# AD5330_Breakout.net
KiCad netlist of a schematic drawn in EAGLE
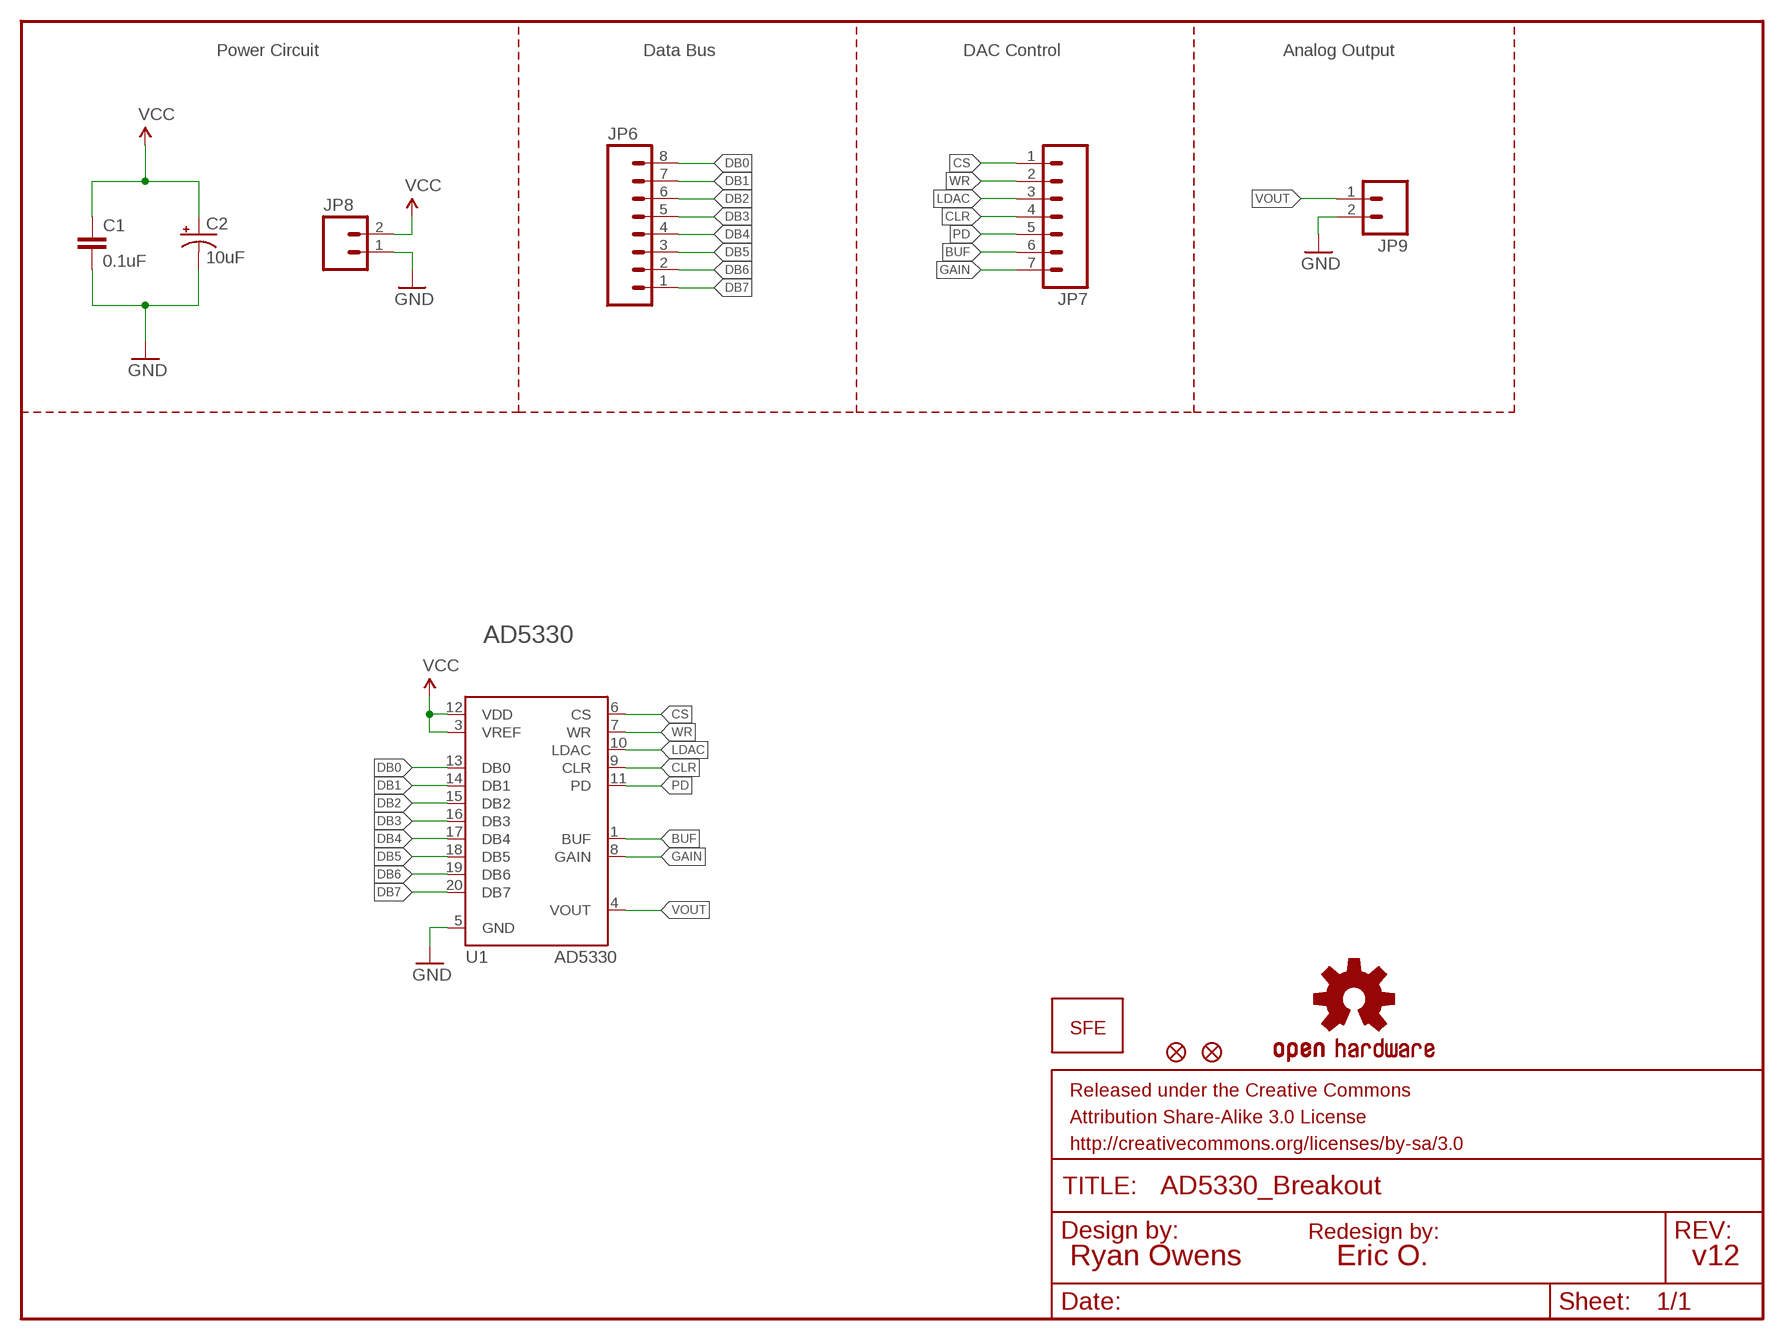
[diagram p0: schematic, sheet 1]

(export (version "E")
  (design (tool "Eeschema 10.0.6"))
  (components
    (comp (ref "C1")
      (value "0.1uF")
      (footprint "eagle-import:0603-CAP")
      (libsource (lib "eagle-import") (part "0.1UF-25V(+80/-20%)(0603)"))
    )
    (comp (ref "C2")
      (value "10uF")
      (footprint "eagle-import:EIA3216")
      (libsource (lib "eagle-import") (part "10UF-16V-10%(TANT)"))
    )
    (comp (ref "FRAME1")
      (value "FRAME-LETTER")
      (footprint "eagle-import:CREATIVE_COMMONS")
      (libsource (lib "eagle-import") (part "FRAME-LETTER"))
    )
    (comp (ref "JP1")
      (value "LOGO-SFENEW")
      (footprint "eagle-import:SFE-NEW-WEBLOGO")
      (libsource (lib "eagle-import") (part "LOGO-SFENEW"))
    )
    (comp (ref "JP2")
      (value "FIDUCIAL1X2")
      (footprint "eagle-import:FIDUCIAL-1X2")
      (libsource (lib "eagle-import") (part "FIDUCIAL1X2"))
    )
    (comp (ref "JP3")
      (value "FIDUCIAL1X2")
      (footprint "eagle-import:FIDUCIAL-1X2")
      (libsource (lib "eagle-import") (part "FIDUCIAL1X2"))
    )
    (comp (ref "JP6")
      (value "M08")
      (footprint "eagle-import:1X08")
      (libsource (lib "eagle-import") (part "M08"))
    )
    (comp (ref "JP7")
      (value "M07")
      (footprint "eagle-import:1X07")
      (libsource (lib "eagle-import") (part "M07"))
    )
    (comp (ref "JP8")
      (value "M02PTH")
      (footprint "eagle-import:1X02")
      (libsource (lib "eagle-import") (part "M02PTH"))
    )
    (comp (ref "JP9")
      (value "M02PTH")
      (footprint "eagle-import:1X02")
      (libsource (lib "eagle-import") (part "M02PTH"))
    )
    (comp (ref "LOGO1")
      (value "OSHW-LOGOS")
      (footprint "eagle-import:OSHW-LOGO-S")
      (libsource (lib "eagle-import") (part "OSHW-LOGOS"))
    )
    (comp (ref "U1")
      (value "AD5330")
      (footprint "eagle-import:TSSOP20")
      (libsource (lib "eagle-import") (part "AD5330"))
    )
  )
  (nets
    (net (code "1") (name "BUF") (class "Default")
      (node (ref "JP7") (pin "6") (pinfunction "6_6") (pintype "passive"))
      (node (ref "U1") (pin "1") (pinfunction "BUF_1") (pintype "bidirectional"))
    )
    (net (code "2") (name "CLR") (class "Default")
      (node (ref "JP7") (pin "4") (pinfunction "4_4") (pintype "passive"))
      (node (ref "U1") (pin "9") (pinfunction "CLR_9") (pintype "bidirectional"))
    )
    (net (code "3") (name "CS") (class "Default")
      (node (ref "JP7") (pin "1") (pinfunction "1_1") (pintype "passive"))
      (node (ref "U1") (pin "6") (pinfunction "CS_6") (pintype "bidirectional"))
    )
    (net (code "4") (name "DB0") (class "Default")
      (node (ref "JP6") (pin "8") (pinfunction "8_8") (pintype "passive"))
      (node (ref "U1") (pin "13") (pinfunction "DB0_13") (pintype "bidirectional"))
    )
    (net (code "5") (name "DB1") (class "Default")
      (node (ref "JP6") (pin "7") (pinfunction "7_7") (pintype "passive"))
      (node (ref "U1") (pin "14") (pinfunction "DB1_14") (pintype "bidirectional"))
    )
    (net (code "6") (name "DB2") (class "Default")
      (node (ref "JP6") (pin "6") (pinfunction "6_6") (pintype "passive"))
      (node (ref "U1") (pin "15") (pinfunction "DB2_15") (pintype "bidirectional"))
    )
    (net (code "7") (name "DB3") (class "Default")
      (node (ref "JP6") (pin "5") (pinfunction "5_5") (pintype "passive"))
      (node (ref "U1") (pin "16") (pinfunction "DB3_16") (pintype "bidirectional"))
    )
    (net (code "8") (name "DB4") (class "Default")
      (node (ref "JP6") (pin "4") (pinfunction "4_4") (pintype "passive"))
      (node (ref "U1") (pin "17") (pinfunction "DB4_17") (pintype "bidirectional"))
    )
    (net (code "9") (name "DB5") (class "Default")
      (node (ref "JP6") (pin "3") (pinfunction "3_3") (pintype "passive"))
      (node (ref "U1") (pin "18") (pinfunction "DB5_18") (pintype "bidirectional"))
    )
    (net (code "10") (name "DB6") (class "Default")
      (node (ref "JP6") (pin "2") (pinfunction "2_2") (pintype "passive"))
      (node (ref "U1") (pin "19") (pinfunction "DB6_19") (pintype "bidirectional"))
    )
    (net (code "11") (name "DB7") (class "Default")
      (node (ref "JP6") (pin "1") (pinfunction "1_1") (pintype "passive"))
      (node (ref "U1") (pin "20") (pinfunction "DB7_20") (pintype "bidirectional"))
    )
    (net (code "12") (name "GAIN") (class "Default")
      (node (ref "JP7") (pin "7") (pinfunction "7_7") (pintype "passive"))
      (node (ref "U1") (pin "8") (pinfunction "GAIN_8") (pintype "bidirectional"))
    )
    (net (code "13") (name "GND") (class "Default")
      (node (ref "C1") (pin "2") (pinfunction "2_2") (pintype "passive"))
      (node (ref "C2") (pin "C") (pinfunction "-_C") (pintype "passive"))
      (node (ref "JP8") (pin "1") (pinfunction "1_1") (pintype "passive"))
      (node (ref "JP9") (pin "2") (pinfunction "2_2") (pintype "passive"))
      (node (ref "U1") (pin "5") (pinfunction "GND_5") (pintype "bidirectional"))
    )
    (net (code "14") (name "LDAC") (class "Default")
      (node (ref "JP7") (pin "3") (pinfunction "3_3") (pintype "passive"))
      (node (ref "U1") (pin "10") (pinfunction "LDAC_10") (pintype "bidirectional"))
    )
    (net (code "15") (name "PD") (class "Default")
      (node (ref "JP7") (pin "5") (pinfunction "5_5") (pintype "passive"))
      (node (ref "U1") (pin "11") (pinfunction "PD_11") (pintype "bidirectional"))
    )
    (net (code "16") (name "VCC") (class "Default")
      (node (ref "C1") (pin "1") (pinfunction "1_1") (pintype "passive"))
      (node (ref "C2") (pin "A") (pinfunction "+_A") (pintype "passive"))
      (node (ref "JP8") (pin "2") (pinfunction "2_2") (pintype "passive"))
      (node (ref "U1") (pin "12") (pinfunction "VDD_12") (pintype "bidirectional"))
      (node (ref "U1") (pin "3") (pinfunction "VREF_3") (pintype "bidirectional"))
    )
    (net (code "17") (name "VOUT") (class "Default")
      (node (ref "JP9") (pin "1") (pinfunction "1_1") (pintype "passive"))
      (node (ref "U1") (pin "4") (pinfunction "VOUT_4") (pintype "bidirectional"))
    )
    (net (code "18") (name "WR") (class "Default")
      (node (ref "JP7") (pin "2") (pinfunction "2_2") (pintype "passive"))
      (node (ref "U1") (pin "7") (pinfunction "WR_7") (pintype "bidirectional"))
    )
  )
)
